# Valve.net
KiCad netlist of a schematic drawn in Altium Designer
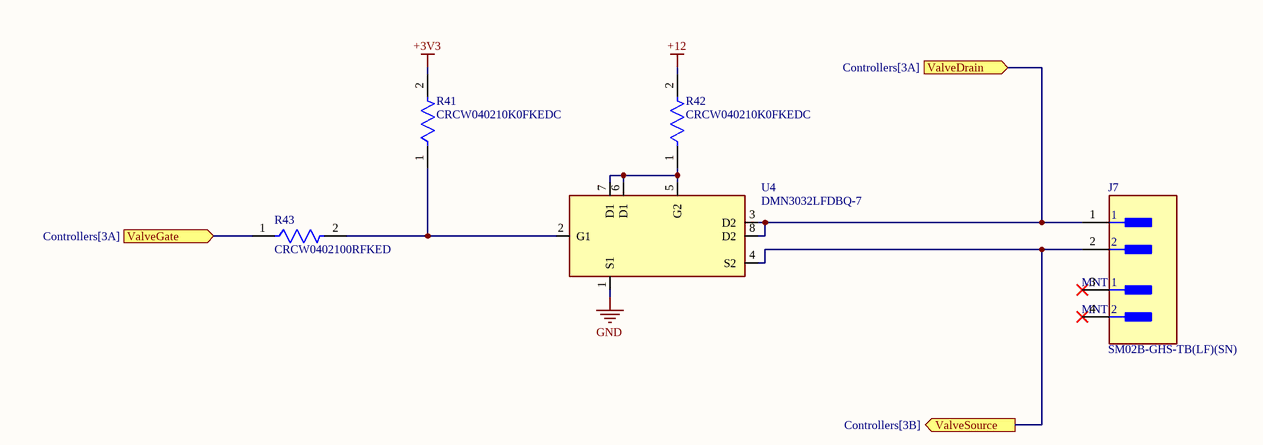
[diagram p0: Valve.SchDoc]

(export (version "E")
  (design (tool "Eeschema 10.0.6"))
  (components
    (comp (ref "J7")
      (value "SM02B-GHS-TB(LF)(SN)")
      (footprint "FP-SM02B-GHS-TB_LF_SN-MFG")
      (description "CONN HEADER SMD R/A 2POS 1.25MM")
      (libsource (lib "Altium Content Vault") (part "56ec3178a87b3978bdc1b3682cd516a"))
    )
    (comp (ref "R41")
      (value "CRCW040210K0FKEDC")
      (footprint "FP-CRCW0402-C-e3-IPC_C")
      (description "RES 10K OHM 1% 1/16W 0402")
      (fields (field (name "TOLERANCE") "1%"))
      (libsource (lib "Altium Content Vault") (part "1029c3af85768c4190bb7ad29bc67b5"))
    )
    (comp (ref "R42")
      (value "CRCW040210K0FKEDC")
      (footprint "FP-CRCW0402-C-e3-IPC_C")
      (description "RES 10K OHM 1% 1/16W 0402")
      (fields (field (name "TOLERANCE") "1%"))
      (libsource (lib "Altium Content Vault") (part "1029c3af85768c4190bb7ad29bc67b5"))
    )
    (comp (ref "R43")
      (value "CRCW0402100RFKED")
      (footprint "FP-CRCW0402-e3-IPC_C")
      (description "RES Thick Film, 100Ω, 1%, 0.063W, 100ppm/°C, 0402")
      (fields (field (name "TOLERANCE") "1%"))
      (libsource (lib "Altium Content Vault") (part "1029c3af85768c4190bb7ad29bc67b5"))
    )
    (comp (ref "U4")
      (value "DMN3032LFDBQ-7")
      (footprint "DMN3032LFDBQ-13")
      (libsource (lib "DMN3032LFDBQ") (part "DMN3032LFDBQ"))
    )
  )
  (nets
    (net (code "1") (name "+3V3") (class "Default")
      (node (ref "R41") (pin "2") (pinfunction "2_2") (pintype "passive"))
    )
    (net (code "2") (name "+12") (class "Default")
      (node (ref "R42") (pin "2") (pinfunction "2_2") (pintype "passive"))
    )
    (net (code "3") (name "/ValveDrain") (class "Default")
      (node (ref "J7") (pin "1") (pinfunction "1_1") (pintype "passive"))
      (node (ref "U4") (pin "3") (pinfunction "D2_3") (pintype "passive"))
      (node (ref "U4") (pin "8") (pinfunction "D2_8") (pintype "passive"))
    )
    (net (code "4") (name "/ValveGate") (class "Default")
      (node (ref "R43") (pin "1") (pinfunction "1_1") (pintype "passive"))
    )
    (net (code "5") (name "/ValveSource") (class "Default")
      (node (ref "J7") (pin "2") (pinfunction "2_2") (pintype "passive"))
      (node (ref "U4") (pin "4") (pinfunction "S2_4") (pintype "passive"))
    )
    (net (code "6") (name "GND") (class "Default")
      (node (ref "U4") (pin "1") (pinfunction "S1_1") (pintype "passive"))
    )
    (net (code "7") (name "Net-(U4-G1)") (class "Default")
      (node (ref "R41") (pin "1") (pinfunction "1_1") (pintype "passive"))
      (node (ref "R43") (pin "2") (pinfunction "2_2") (pintype "passive"))
      (node (ref "U4") (pin "2") (pinfunction "G1_2") (pintype "passive"))
    )
    (net (code "8") (name "Net-(U4-G2)") (class "Default")
      (node (ref "R42") (pin "1") (pinfunction "1_1") (pintype "passive"))
      (node (ref "U4") (pin "5") (pinfunction "G2_5") (pintype "passive"))
      (node (ref "U4") (pin "6") (pinfunction "D1_6") (pintype "passive"))
      (node (ref "U4") (pin "7") (pinfunction "D1_7") (pintype "passive"))
    )
    (net (code "9") (name "unconnected-(J7-MNT_1-Pad3)") (class "Default")
      (node (ref "J7") (pin "3") (pinfunction "MNT_1_3") (pintype "passive+no_connect"))
    )
    (net (code "10") (name "unconnected-(J7-MNT_2-Pad4)") (class "Default")
      (node (ref "J7") (pin "4") (pinfunction "MNT_2_4") (pintype "passive+no_connect"))
    )
  )
)
